# lcd240.net
KiCad netlist of a schematic drawn in EAGLE
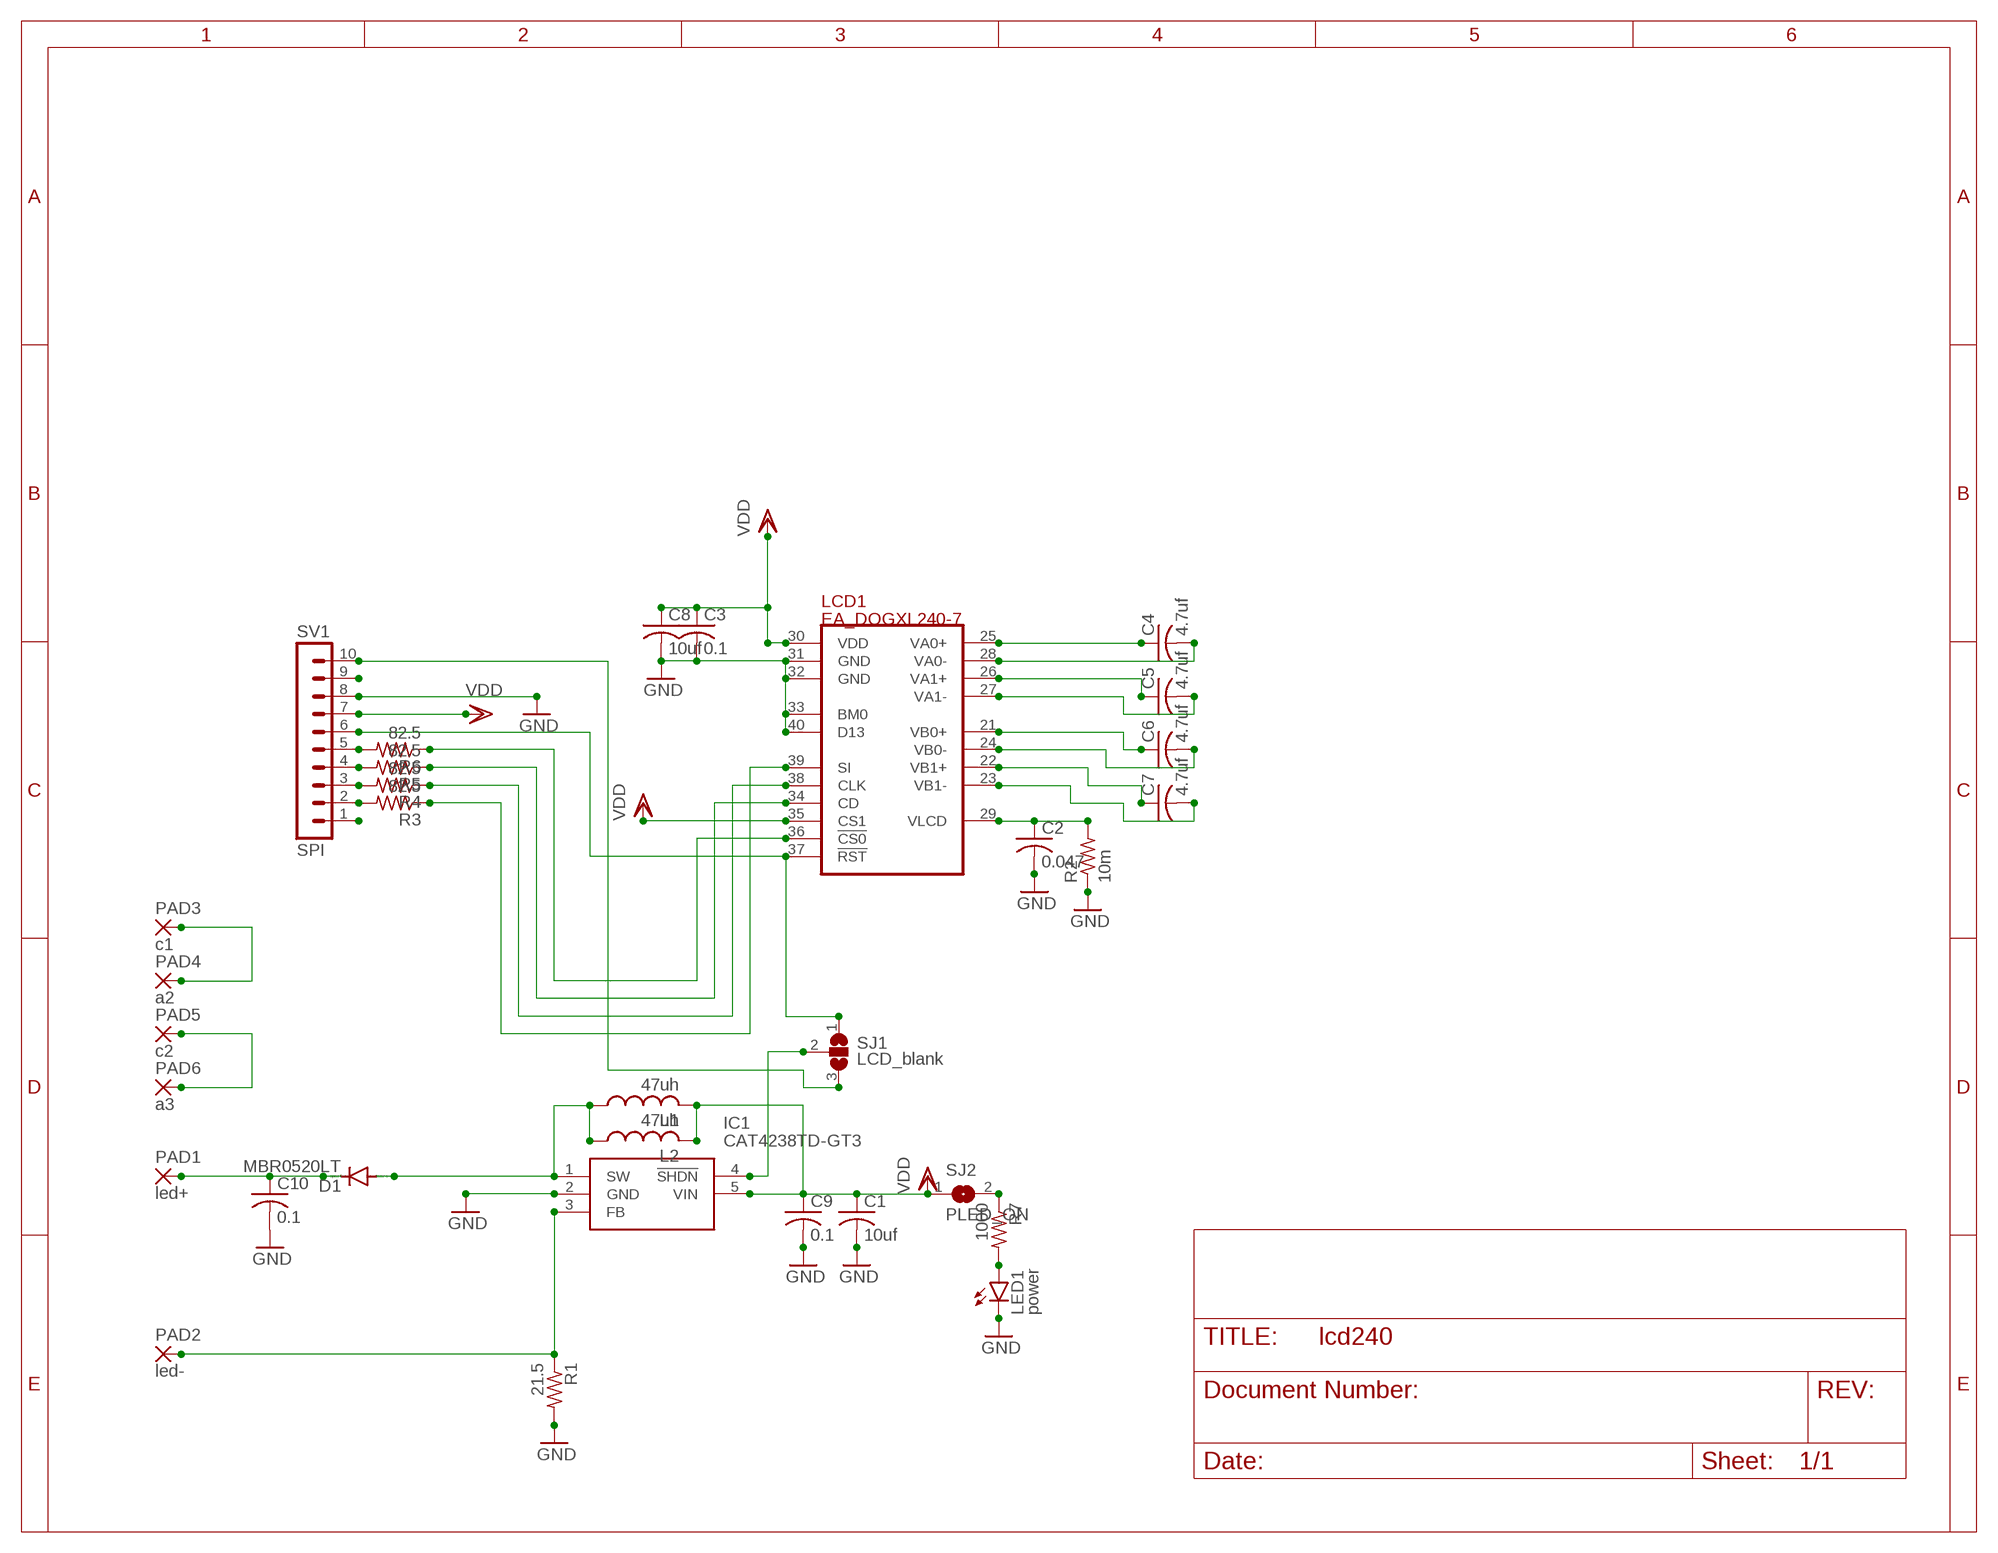
[diagram p0: schematic, sheet 1]

(export (version "E")
  (design (tool "Eeschema 10.0.6"))
  (components
    (comp (ref "C1")
      (value "10uf")
      (footprint "eagle-import:C1206")
      (libsource (lib "eagle-import") (part "C-USC1206"))
    )
    (comp (ref "C2")
      (value "0.047")
      (footprint "eagle-import:C1206")
      (libsource (lib "eagle-import") (part "C-USC1206"))
    )
    (comp (ref "C3")
      (value "0.1")
      (footprint "eagle-import:C1206")
      (libsource (lib "eagle-import") (part "C-USC1206"))
    )
    (comp (ref "C4")
      (value "4.7uf")
      (footprint "eagle-import:C1206")
      (libsource (lib "eagle-import") (part "C-USC1206"))
    )
    (comp (ref "C5")
      (value "4.7uf")
      (footprint "eagle-import:C1206")
      (libsource (lib "eagle-import") (part "C-USC1206"))
    )
    (comp (ref "C6")
      (value "4.7uf")
      (footprint "eagle-import:C1206")
      (libsource (lib "eagle-import") (part "C-USC1206"))
    )
    (comp (ref "C7")
      (value "4.7uf")
      (footprint "eagle-import:C1206")
      (libsource (lib "eagle-import") (part "C-USC1206"))
    )
    (comp (ref "C8")
      (value "10uf")
      (footprint "eagle-import:C1206")
      (libsource (lib "eagle-import") (part "C-USC1206"))
    )
    (comp (ref "C9")
      (value "0.1")
      (footprint "eagle-import:C1206")
      (libsource (lib "eagle-import") (part "C-USC1206"))
    )
    (comp (ref "C10")
      (value "0.1")
      (footprint "eagle-import:C1206")
      (libsource (lib "eagle-import") (part "C-USC1206"))
    )
    (comp (ref "D1")
      (value "MBR0520LT")
      (footprint "eagle-import:SOD123")
      (libsource (lib "eagle-import") (part "MBR0520LT"))
    )
    (comp (ref "IC1")
      (value "CAT4238TD-GT3")
      (footprint "eagle-import:SOT95P280X100-5N")
      (fields (field (name "MOUSER_PART_NUMBER") "698-CAT4238TDG"))
      (libsource (lib "eagle-import") (part "CAT4238TD-GT3"))
    )
    (comp (ref "L1")
      (value "47uh")
      (footprint "eagle-import:0204_5")
      (libsource (lib "eagle-import") (part "L-US0204/5"))
    )
    (comp (ref "L2")
      (value "47uh")
      (footprint "eagle-import:L2012C")
      (libsource (lib "eagle-import") (part "L-USL2012C"))
    )
    (comp (ref "LCD1")
      (value "EA_DOGXL240-7")
      (footprint "eagle-import:EA_DOGXL240-7")
      (libsource (lib "eagle-import") (part "EA_DOGXL240-7"))
    )
    (comp (ref "LED1")
      (value "power")
      (footprint "eagle-import:SML0805")
      (libsource (lib "eagle-import") (part "LEDSML0805"))
    )
    (comp (ref "PAD1")
      (value "led+")
      (footprint "eagle-import:1,6_0,8")
      (libsource (lib "eagle-import") (part "1,6/0,8"))
    )
    (comp (ref "PAD2")
      (value "led-")
      (footprint "eagle-import:1,6_0,8")
      (libsource (lib "eagle-import") (part "1,6/0,8"))
    )
    (comp (ref "PAD3")
      (value "c1")
      (footprint "eagle-import:1,6_0,8")
      (libsource (lib "eagle-import") (part "1,6/0,8"))
    )
    (comp (ref "PAD4")
      (value "a2")
      (footprint "eagle-import:1,6_0,8")
      (libsource (lib "eagle-import") (part "1,6/0,8"))
    )
    (comp (ref "PAD5")
      (value "c2")
      (footprint "eagle-import:1,6_0,8")
      (libsource (lib "eagle-import") (part "1,6/0,8"))
    )
    (comp (ref "PAD6")
      (value "a3")
      (footprint "eagle-import:1,6_0,8")
      (libsource (lib "eagle-import") (part "1,6/0,8"))
    )
    (comp (ref "R1")
      (value "21.5")
      (footprint "eagle-import:R0805")
      (libsource (lib "eagle-import") (part "R-US_R0805"))
    )
    (comp (ref "R2")
      (value "10m")
      (footprint "eagle-import:R0805")
      (libsource (lib "eagle-import") (part "R-US_R0805"))
    )
    (comp (ref "R3")
      (value "82.5")
      (footprint "eagle-import:R0805")
      (libsource (lib "eagle-import") (part "R-US_R0805"))
    )
    (comp (ref "R4")
      (value "82.5")
      (footprint "eagle-import:R0805")
      (libsource (lib "eagle-import") (part "R-US_R0805"))
    )
    (comp (ref "R5")
      (value "82.5")
      (footprint "eagle-import:R0805")
      (libsource (lib "eagle-import") (part "R-US_R0805"))
    )
    (comp (ref "R6")
      (value "82.5")
      (footprint "eagle-import:R0805")
      (libsource (lib "eagle-import") (part "R-US_R0805"))
    )
    (comp (ref "R7")
      (value "1000")
      (footprint "eagle-import:R0805")
      (libsource (lib "eagle-import") (part "R-US_R0805"))
    )
    (comp (ref "SJ1")
      (value "LCD_blank")
      (footprint "eagle-import:SJ_2")
      (libsource (lib "eagle-import") (part "SJ2W"))
    )
    (comp (ref "SJ2")
      (value "PLED_ON")
      (footprint "eagle-import:SJ")
      (libsource (lib "eagle-import") (part "SJ"))
    )
    (comp (ref "SV1")
      (value "SPI")
      (footprint "eagle-import:MA10-1")
      (libsource (lib "eagle-import") (part "MA10-1"))
    )
  )
  (nets
    (net (code "1") (name "GND") (class "Default")
      (node (ref "C1") (pin "2") (pinfunction "2_2") (pintype "passive"))
      (node (ref "C10") (pin "2") (pinfunction "2_2") (pintype "passive"))
      (node (ref "C2") (pin "2") (pinfunction "2_2") (pintype "passive"))
      (node (ref "C3") (pin "2") (pinfunction "2_2") (pintype "passive"))
      (node (ref "C8") (pin "2") (pinfunction "2_2") (pintype "passive"))
      (node (ref "C9") (pin "2") (pinfunction "2_2") (pintype "passive"))
      (node (ref "IC1") (pin "2") (pinfunction "GND_2") (pintype "power_in"))
      (node (ref "LCD1") (pin "31") (pinfunction "GND_31") (pintype "power_in"))
      (node (ref "LCD1") (pin "32") (pinfunction "GND_32") (pintype "power_in"))
      (node (ref "LCD1") (pin "33") (pinfunction "BM0_33") (pintype "input"))
      (node (ref "LCD1") (pin "40") (pinfunction "D13_40") (pintype "input"))
      (node (ref "LED1") (pin "C") (pinfunction "C_C") (pintype "passive"))
      (node (ref "R1") (pin "2") (pinfunction "2_2") (pintype "passive"))
      (node (ref "R2") (pin "1") (pinfunction "1_1") (pintype "passive"))
      (node (ref "SV1") (pin "8") (pinfunction "8_8") (pintype "passive"))
    )
    (net (code "2") (name "Net-(IC1-FB)") (class "Default")
      (node (ref "IC1") (pin "3") (pinfunction "FB_3") (pintype "bidirectional"))
      (node (ref "PAD2") (pin "1") (pinfunction "P_1") (pintype "passive"))
      (node (ref "R1") (pin "1") (pinfunction "1_1") (pintype "passive"))
    )
    (net (code "3") (name "Net-(IC1-SW)") (class "Default")
      (node (ref "D1") (pin "A") (pinfunction "A_A") (pintype "passive"))
      (node (ref "IC1") (pin "1") (pinfunction "SW_1") (pintype "bidirectional"))
      (node (ref "L1") (pin "1") (pinfunction "1_1") (pintype "passive"))
      (node (ref "L2") (pin "1") (pinfunction "1_1") (pintype "passive"))
    )
    (net (code "4") (name "Net-(IC1-~{SHDN})") (class "Default")
      (node (ref "IC1") (pin "4") (pinfunction "~{SHDN}_4") (pintype "bidirectional"))
      (node (ref "SJ1") (pin "2") (pinfunction "2_2") (pintype "passive"))
    )
    (net (code "5") (name "Net-(LCD1-CD)") (class "Default")
      (node (ref "LCD1") (pin "34") (pinfunction "CD_34") (pintype "input"))
      (node (ref "R5") (pin "1") (pinfunction "1_1") (pintype "passive"))
    )
    (net (code "6") (name "Net-(LCD1-CLK)") (class "Default")
      (node (ref "LCD1") (pin "38") (pinfunction "CLK_38") (pintype "input"))
      (node (ref "R4") (pin "1") (pinfunction "1_1") (pintype "passive"))
    )
    (net (code "7") (name "Net-(LCD1-SI)") (class "Default")
      (node (ref "LCD1") (pin "39") (pinfunction "SI_39") (pintype "input"))
      (node (ref "R3") (pin "1") (pinfunction "1_1") (pintype "passive"))
    )
    (net (code "8") (name "Net-(LCD1-VA0+)") (class "Default")
      (node (ref "C4") (pin "1") (pinfunction "1_1") (pintype "passive"))
      (node (ref "LCD1") (pin "25") (pinfunction "VA0+_25") (pintype "passive"))
    )
    (net (code "9") (name "Net-(LCD1-VA0-)") (class "Default")
      (node (ref "C4") (pin "2") (pinfunction "2_2") (pintype "passive"))
      (node (ref "LCD1") (pin "28") (pinfunction "VA0-_28") (pintype "passive"))
    )
    (net (code "10") (name "Net-(LCD1-VA1+)") (class "Default")
      (node (ref "C5") (pin "1") (pinfunction "1_1") (pintype "passive"))
      (node (ref "LCD1") (pin "26") (pinfunction "VA1+_26") (pintype "passive"))
    )
    (net (code "11") (name "Net-(LCD1-VA1-)") (class "Default")
      (node (ref "C5") (pin "2") (pinfunction "2_2") (pintype "passive"))
      (node (ref "LCD1") (pin "27") (pinfunction "VA1-_27") (pintype "passive"))
    )
    (net (code "12") (name "Net-(LCD1-VB0+)") (class "Default")
      (node (ref "C6") (pin "1") (pinfunction "1_1") (pintype "passive"))
      (node (ref "LCD1") (pin "21") (pinfunction "VB0+_21") (pintype "passive"))
    )
    (net (code "13") (name "Net-(LCD1-VB0-)") (class "Default")
      (node (ref "C6") (pin "2") (pinfunction "2_2") (pintype "passive"))
      (node (ref "LCD1") (pin "24") (pinfunction "VB0-_24") (pintype "passive"))
    )
    (net (code "14") (name "Net-(LCD1-VB1+)") (class "Default")
      (node (ref "C7") (pin "1") (pinfunction "1_1") (pintype "passive"))
      (node (ref "LCD1") (pin "22") (pinfunction "VB1+_22") (pintype "passive"))
    )
    (net (code "15") (name "Net-(LCD1-VB1-)") (class "Default")
      (node (ref "C7") (pin "2") (pinfunction "2_2") (pintype "passive"))
      (node (ref "LCD1") (pin "23") (pinfunction "VB1-_23") (pintype "passive"))
    )
    (net (code "16") (name "Net-(LCD1-VLCD)") (class "Default")
      (node (ref "C2") (pin "1") (pinfunction "1_1") (pintype "passive"))
      (node (ref "LCD1") (pin "29") (pinfunction "VLCD_29") (pintype "passive"))
      (node (ref "R2") (pin "2") (pinfunction "2_2") (pintype "passive"))
    )
    (net (code "17") (name "Net-(LCD1-~{CS0})") (class "Default")
      (node (ref "LCD1") (pin "36") (pinfunction "~{CS0}_36") (pintype "input"))
      (node (ref "R6") (pin "1") (pinfunction "1_1") (pintype "passive"))
    )
    (net (code "18") (name "Net-(LCD1-~{RST})") (class "Default")
      (node (ref "LCD1") (pin "37") (pinfunction "~{RST}_37") (pintype "input"))
      (node (ref "SJ1") (pin "1") (pinfunction "1_1") (pintype "passive"))
      (node (ref "SV1") (pin "6") (pinfunction "6_6") (pintype "passive"))
    )
    (net (code "19") (name "Net-(LED1-PadA)") (class "Default")
      (node (ref "LED1") (pin "A") (pinfunction "A_A") (pintype "passive"))
      (node (ref "R7") (pin "2") (pinfunction "2_2") (pintype "passive"))
    )
    (net (code "20") (name "Net-(PAD1-P)") (class "Default")
      (node (ref "C10") (pin "1") (pinfunction "1_1") (pintype "passive"))
      (node (ref "D1") (pin "C") (pinfunction "C_C") (pintype "passive"))
      (node (ref "PAD1") (pin "1") (pinfunction "P_1") (pintype "passive"))
    )
    (net (code "21") (name "Net-(PAD3-P)") (class "Default")
      (node (ref "PAD3") (pin "1") (pinfunction "P_1") (pintype "passive"))
      (node (ref "PAD4") (pin "1") (pinfunction "P_1") (pintype "passive"))
    )
    (net (code "22") (name "Net-(PAD5-P)") (class "Default")
      (node (ref "PAD5") (pin "1") (pinfunction "P_1") (pintype "passive"))
      (node (ref "PAD6") (pin "1") (pinfunction "P_1") (pintype "passive"))
    )
    (net (code "23") (name "Net-(R3-Pad2)") (class "Default")
      (node (ref "R3") (pin "2") (pinfunction "2_2") (pintype "passive"))
      (node (ref "SV1") (pin "2") (pinfunction "2_2") (pintype "passive"))
    )
    (net (code "24") (name "Net-(R4-Pad2)") (class "Default")
      (node (ref "R4") (pin "2") (pinfunction "2_2") (pintype "passive"))
      (node (ref "SV1") (pin "3") (pinfunction "3_3") (pintype "passive"))
    )
    (net (code "25") (name "Net-(R5-Pad2)") (class "Default")
      (node (ref "R5") (pin "2") (pinfunction "2_2") (pintype "passive"))
      (node (ref "SV1") (pin "4") (pinfunction "4_4") (pintype "passive"))
    )
    (net (code "26") (name "Net-(R6-Pad2)") (class "Default")
      (node (ref "R6") (pin "2") (pinfunction "2_2") (pintype "passive"))
      (node (ref "SV1") (pin "5") (pinfunction "5_5") (pintype "passive"))
    )
    (net (code "27") (name "Net-(R7-Pad1)") (class "Default")
      (node (ref "R7") (pin "1") (pinfunction "1_1") (pintype "passive"))
      (node (ref "SJ2") (pin "2") (pinfunction "2_2") (pintype "passive"))
    )
    (net (code "28") (name "Net-(SJ1-Pad3)") (class "Default")
      (node (ref "SJ1") (pin "3") (pinfunction "3_3") (pintype "passive"))
      (node (ref "SV1") (pin "10") (pinfunction "10_10") (pintype "passive"))
    )
    (net (code "29") (name "VDD") (class "Default")
      (node (ref "C1") (pin "1") (pinfunction "1_1") (pintype "passive"))
      (node (ref "C3") (pin "1") (pinfunction "1_1") (pintype "passive"))
      (node (ref "C8") (pin "1") (pinfunction "1_1") (pintype "passive"))
      (node (ref "C9") (pin "1") (pinfunction "1_1") (pintype "passive"))
      (node (ref "IC1") (pin "5") (pinfunction "VIN_5") (pintype "input"))
      (node (ref "L1") (pin "2") (pinfunction "2_2") (pintype "passive"))
      (node (ref "L2") (pin "2") (pinfunction "2_2") (pintype "passive"))
      (node (ref "LCD1") (pin "30") (pinfunction "VDD_30") (pintype "power_in"))
      (node (ref "LCD1") (pin "35") (pinfunction "CS1_35") (pintype "input"))
      (node (ref "SJ2") (pin "1") (pinfunction "1_1") (pintype "passive"))
      (node (ref "SV1") (pin "7") (pinfunction "7_7") (pintype "passive"))
    )
    (net (code "30") (name "unconnected-(SV1-Pad1)") (class "Default")
      (node (ref "SV1") (pin "1") (pinfunction "1_1") (pintype "passive"))
    )
    (net (code "31") (name "unconnected-(SV1-Pad9)") (class "Default")
      (node (ref "SV1") (pin "9") (pinfunction "9_9") (pintype "passive"))
    )
  )
)
